# 9DoF_IMU_Module.net
KiCad netlist of a schematic drawn in EAGLE
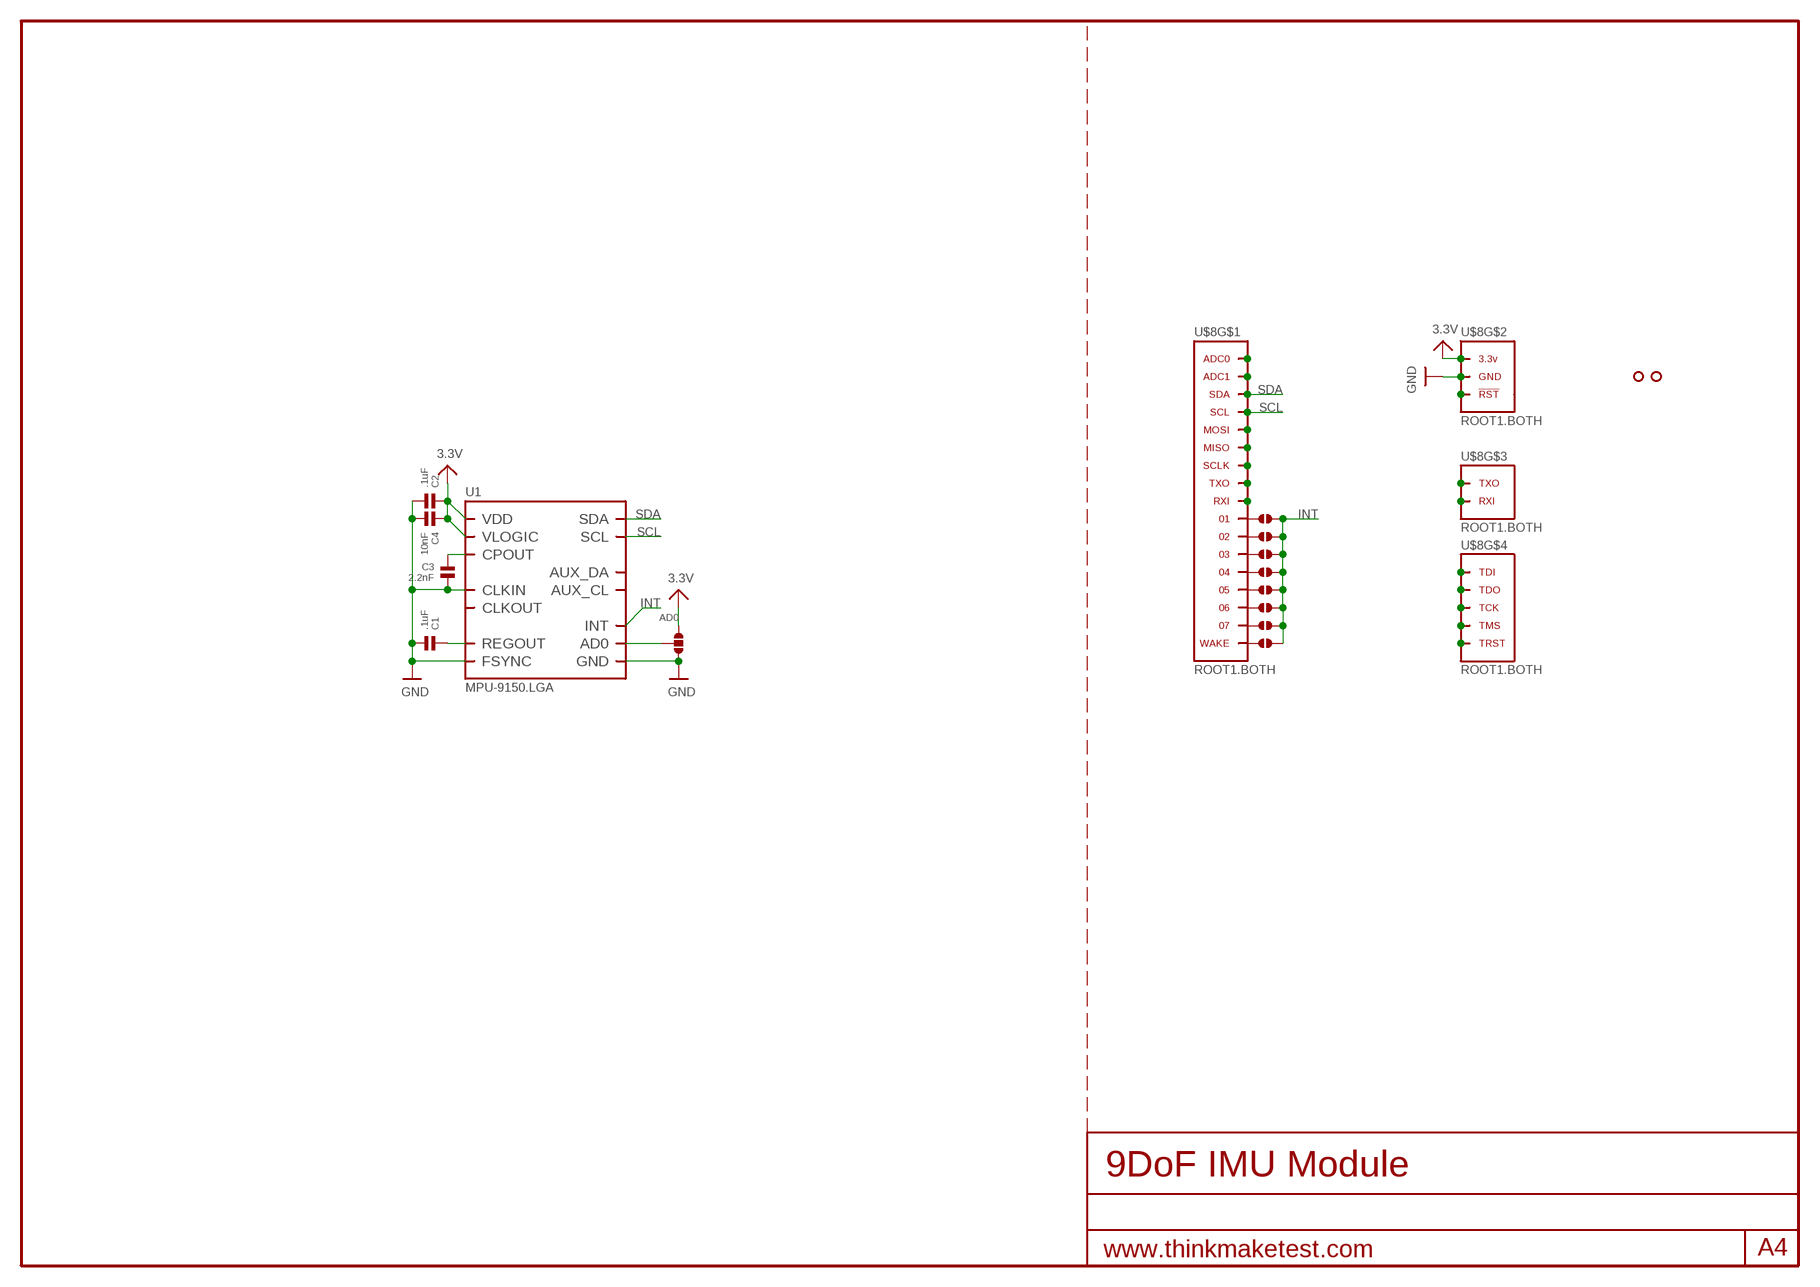
[diagram p0: schematic, sheet 1]

(export (version "E")
  (design (tool "Eeschema 10.0.6"))
  (components
    (comp (ref "AD0")
      (value "SOLDERJUMPER.3.MED.23")
      (footprint "eagle-import:3.MED.23")
      (libsource (lib "eagle-import") (part "SOLDERJUMPER.3.MED.23"))
    )
    (comp (ref "C1")
      (value ".1uF")
      (footprint "eagle-import:0603")
      (libsource (lib "eagle-import") (part "CAPACITOR.0603"))
    )
    (comp (ref "C2")
      (value ".1uF")
      (footprint "eagle-import:0603")
      (libsource (lib "eagle-import") (part "CAPACITOR.0603"))
    )
    (comp (ref "C3")
      (value "2.2nF")
      (footprint "eagle-import:0603")
      (libsource (lib "eagle-import") (part "CAPACITOR.0603"))
    )
    (comp (ref "C4")
      (value "10nF")
      (footprint "eagle-import:0603")
      (libsource (lib "eagle-import") (part "CAPACITOR.0603"))
    )
    (comp (ref "J1")
      (value "SOLDERJUMPER.2.SML")
      (footprint "eagle-import:2.SML")
      (libsource (lib "eagle-import") (part "SOLDERJUMPER.2.SML"))
    )
    (comp (ref "J2")
      (value "SOLDERJUMPER.2.SML")
      (footprint "eagle-import:2.SML")
      (libsource (lib "eagle-import") (part "SOLDERJUMPER.2.SML"))
    )
    (comp (ref "J3")
      (value "SOLDERJUMPER.2.SML")
      (footprint "eagle-import:2.SML")
      (libsource (lib "eagle-import") (part "SOLDERJUMPER.2.SML"))
    )
    (comp (ref "J4")
      (value "SOLDERJUMPER.2.SML")
      (footprint "eagle-import:2.SML")
      (libsource (lib "eagle-import") (part "SOLDERJUMPER.2.SML"))
    )
    (comp (ref "J5")
      (value "SOLDERJUMPER.2.SML")
      (footprint "eagle-import:2.SML")
      (libsource (lib "eagle-import") (part "SOLDERJUMPER.2.SML"))
    )
    (comp (ref "J6")
      (value "SOLDERJUMPER.2.SML")
      (footprint "eagle-import:2.SML")
      (libsource (lib "eagle-import") (part "SOLDERJUMPER.2.SML"))
    )
    (comp (ref "J7")
      (value "SOLDERJUMPER.2.SML")
      (footprint "eagle-import:2.SML")
      (libsource (lib "eagle-import") (part "SOLDERJUMPER.2.SML"))
    )
    (comp (ref "J8")
      (value "SOLDERJUMPER.2.SML")
      (footprint "eagle-import:2.SML")
      (libsource (lib "eagle-import") (part "SOLDERJUMPER.2.SML"))
    )
    (comp (ref "U$2")
      (value "HOLE.#2")
      (footprint "eagle-import:#2")
      (libsource (lib "eagle-import") (part "HOLE.#2"))
    )
    (comp (ref "U$8")
      (value "ROOT1.BOTH")
      (footprint "eagle-import:ROOT1.BOTH")
      (libsource (lib "eagle-import") (part "ROOT1.BOTH"))
    )
    (comp (ref "U$12")
      (value "HOLE.#2")
      (footprint "eagle-import:#2")
      (libsource (lib "eagle-import") (part "HOLE.#2"))
    )
    (comp (ref "U1")
      (value "MPU-9150.LGA")
      (footprint "eagle-import:LGA.24.4X4")
      (libsource (lib "eagle-import") (part "MPU-9150.LGA"))
    )
  )
  (nets
    (net (code "1") (name "/INT") (class "Default")
      (node (ref "J1") (pin "2") (pinfunction "2_2") (pintype "bidirectional"))
      (node (ref "J2") (pin "2") (pinfunction "2_2") (pintype "bidirectional"))
      (node (ref "J3") (pin "2") (pinfunction "2_2") (pintype "bidirectional"))
      (node (ref "J4") (pin "2") (pinfunction "2_2") (pintype "bidirectional"))
      (node (ref "J5") (pin "2") (pinfunction "2_2") (pintype "bidirectional"))
      (node (ref "J6") (pin "2") (pinfunction "2_2") (pintype "bidirectional"))
      (node (ref "J7") (pin "2") (pinfunction "2_2") (pintype "bidirectional"))
      (node (ref "J8") (pin "2") (pinfunction "2_2") (pintype "bidirectional"))
      (node (ref "U1") (pin "12") (pinfunction "INT_12") (pintype "bidirectional"))
    )
    (net (code "2") (name "/SCL") (class "Default")
      (node (ref "U$8") (pin "SCL") (pinfunction "SCL_SCL") (pintype "bidirectional"))
      (node (ref "U$8") (pin "SCL@1") (pinfunction "SCL_SCL@1") (pintype "bidirectional"))
      (node (ref "U$8") (pin "SCL@VIA") (pinfunction "SCL_SCL@VIA") (pintype "bidirectional"))
      (node (ref "U1") (pin "23") (pinfunction "SCL_23") (pintype "bidirectional"))
    )
    (net (code "3") (name "/SDA") (class "Default")
      (node (ref "U$8") (pin "SDA") (pinfunction "SDA_SDA") (pintype "bidirectional"))
      (node (ref "U$8") (pin "SDA@1") (pinfunction "SDA_SDA@1") (pintype "bidirectional"))
      (node (ref "U$8") (pin "SDA@VIA") (pinfunction "SDA_SDA@VIA") (pintype "bidirectional"))
      (node (ref "U1") (pin "24") (pinfunction "SDA_24") (pintype "bidirectional"))
    )
    (net (code "4") (name "3.3V") (class "Default")
      (node (ref "AD0") (pin "1") (pinfunction "1_1") (pintype "bidirectional"))
      (node (ref "C2") (pin "1") (pinfunction "1_1") (pintype "bidirectional"))
      (node (ref "C4") (pin "1") (pinfunction "1_1") (pintype "bidirectional"))
      (node (ref "U$8") (pin "3.3V@1") (pinfunction "3.3V_3.3V@1") (pintype "bidirectional"))
      (node (ref "U$8") (pin "3.3V@10") (pinfunction "3.3V_3.3V@10") (pintype "bidirectional"))
      (node (ref "U$8") (pin "3.3V@11") (pinfunction "3.3V_3.3V@11") (pintype "bidirectional"))
      (node (ref "U$8") (pin "3.3V@12") (pinfunction "3.3V_3.3V@12") (pintype "bidirectional"))
      (node (ref "U$8") (pin "3.3V@13") (pinfunction "3.3V_3.3V@13") (pintype "bidirectional"))
      (node (ref "U$8") (pin "3.3V@14") (pinfunction "3.3V_3.3V@14") (pintype "bidirectional"))
      (node (ref "U$8") (pin "3.3V@15") (pinfunction "3.3V_3.3V@15") (pintype "bidirectional"))
      (node (ref "U$8") (pin "3.3V@16") (pinfunction "3.3V_3.3V@16") (pintype "bidirectional"))
      (node (ref "U$8") (pin "3.3V@17") (pinfunction "3.3V_3.3V@17") (pintype "bidirectional"))
      (node (ref "U$8") (pin "3.3V@18") (pinfunction "3.3V_3.3V@18") (pintype "bidirectional"))
      (node (ref "U$8") (pin "3.3V@19") (pinfunction "3.3V_3.3V@19") (pintype "bidirectional"))
      (node (ref "U$8") (pin "3.3V@2") (pinfunction "3.3V_3.3V@2") (pintype "bidirectional"))
      (node (ref "U$8") (pin "3.3V@20") (pinfunction "3.3V_3.3V@20") (pintype "bidirectional"))
      (node (ref "U$8") (pin "3.3V@21") (pinfunction "3.3V_3.3V@21") (pintype "bidirectional"))
      (node (ref "U$8") (pin "3.3V@22") (pinfunction "3.3V_3.3V@22") (pintype "bidirectional"))
      (node (ref "U$8") (pin "3.3V@23") (pinfunction "3.3V_3.3V@23") (pintype "bidirectional"))
      (node (ref "U$8") (pin "3.3V@24") (pinfunction "3.3V_3.3V@24") (pintype "bidirectional"))
      (node (ref "U$8") (pin "3.3V@3") (pinfunction "3.3V_3.3V@3") (pintype "bidirectional"))
      (node (ref "U$8") (pin "3.3V@4") (pinfunction "3.3V_3.3V@4") (pintype "bidirectional"))
      (node (ref "U$8") (pin "3.3V@5") (pinfunction "3.3V_3.3V@5") (pintype "bidirectional"))
      (node (ref "U$8") (pin "3.3V@6") (pinfunction "3.3V_3.3V@6") (pintype "bidirectional"))
      (node (ref "U$8") (pin "3.3V@7") (pinfunction "3.3V_3.3V@7") (pintype "bidirectional"))
      (node (ref "U$8") (pin "3.3V@8") (pinfunction "3.3V_3.3V@8") (pintype "bidirectional"))
      (node (ref "U$8") (pin "3.3V@9") (pinfunction "3.3V_3.3V@9") (pintype "bidirectional"))
      (node (ref "U$8") (pin "3.3V@VIA") (pinfunction "3.3V_3.3V@VIA") (pintype "bidirectional"))
      (node (ref "U1") (pin "13") (pinfunction "VDD_13") (pintype "bidirectional"))
      (node (ref "U1") (pin "3") (pinfunction "VDD_3") (pintype "bidirectional"))
      (node (ref "U1") (pin "8") (pinfunction "VLOGIC_8") (pintype "bidirectional"))
    )
    (net (code "5") (name "GND") (class "Default")
      (node (ref "AD0") (pin "3") (pinfunction "3_3") (pintype "bidirectional"))
      (node (ref "C1") (pin "2") (pinfunction "2_2") (pintype "bidirectional"))
      (node (ref "C2") (pin "2") (pinfunction "2_2") (pintype "bidirectional"))
      (node (ref "C3") (pin "2") (pinfunction "2_2") (pintype "bidirectional"))
      (node (ref "C4") (pin "2") (pinfunction "2_2") (pintype "bidirectional"))
      (node (ref "U$8") (pin "GND@1") (pinfunction "GND_GND@1") (pintype "bidirectional"))
      (node (ref "U$8") (pin "GND@10") (pinfunction "GND_GND@10") (pintype "bidirectional"))
      (node (ref "U$8") (pin "GND@11") (pinfunction "GND_GND@11") (pintype "bidirectional"))
      (node (ref "U$8") (pin "GND@12") (pinfunction "GND_GND@12") (pintype "bidirectional"))
      (node (ref "U$8") (pin "GND@13") (pinfunction "GND_GND@13") (pintype "bidirectional"))
      (node (ref "U$8") (pin "GND@14") (pinfunction "GND_GND@14") (pintype "bidirectional"))
      (node (ref "U$8") (pin "GND@15") (pinfunction "GND_GND@15") (pintype "bidirectional"))
      (node (ref "U$8") (pin "GND@16") (pinfunction "GND_GND@16") (pintype "bidirectional"))
      (node (ref "U$8") (pin "GND@17") (pinfunction "GND_GND@17") (pintype "bidirectional"))
      (node (ref "U$8") (pin "GND@18") (pinfunction "GND_GND@18") (pintype "bidirectional"))
      (node (ref "U$8") (pin "GND@19") (pinfunction "GND_GND@19") (pintype "bidirectional"))
      (node (ref "U$8") (pin "GND@2") (pinfunction "GND_GND@2") (pintype "bidirectional"))
      (node (ref "U$8") (pin "GND@20") (pinfunction "GND_GND@20") (pintype "bidirectional"))
      (node (ref "U$8") (pin "GND@21") (pinfunction "GND_GND@21") (pintype "bidirectional"))
      (node (ref "U$8") (pin "GND@22") (pinfunction "GND_GND@22") (pintype "bidirectional"))
      (node (ref "U$8") (pin "GND@23") (pinfunction "GND_GND@23") (pintype "bidirectional"))
      (node (ref "U$8") (pin "GND@24") (pinfunction "GND_GND@24") (pintype "bidirectional"))
      (node (ref "U$8") (pin "GND@25") (pinfunction "GND_GND@25") (pintype "bidirectional"))
      (node (ref "U$8") (pin "GND@26") (pinfunction "GND_GND@26") (pintype "bidirectional"))
      (node (ref "U$8") (pin "GND@3") (pinfunction "GND_GND@3") (pintype "bidirectional"))
      (node (ref "U$8") (pin "GND@4") (pinfunction "GND_GND@4") (pintype "bidirectional"))
      (node (ref "U$8") (pin "GND@5") (pinfunction "GND_GND@5") (pintype "bidirectional"))
      (node (ref "U$8") (pin "GND@6") (pinfunction "GND_GND@6") (pintype "bidirectional"))
      (node (ref "U$8") (pin "GND@7") (pinfunction "GND_GND@7") (pintype "bidirectional"))
      (node (ref "U$8") (pin "GND@8") (pinfunction "GND_GND@8") (pintype "bidirectional"))
      (node (ref "U$8") (pin "GND@9") (pinfunction "GND_GND@9") (pintype "bidirectional"))
      (node (ref "U$8") (pin "GND@VIA") (pinfunction "GND_GND@VIA") (pintype "bidirectional"))
      (node (ref "U1") (pin "1") (pinfunction "CLKIN_1") (pintype "bidirectional"))
      (node (ref "U1") (pin "11") (pinfunction "FSYNC_11") (pintype "bidirectional"))
      (node (ref "U1") (pin "15") (pinfunction "GND_15") (pintype "bidirectional"))
      (node (ref "U1") (pin "17") (pinfunction "GND_17") (pintype "bidirectional"))
      (node (ref "U1") (pin "18") (pinfunction "GND_18") (pintype "bidirectional"))
    )
    (net (code "6") (name "Net-(J1-Pad1)") (class "Default")
      (node (ref "J1") (pin "1") (pinfunction "1_1") (pintype "bidirectional"))
      (node (ref "U$8") (pin "01") (pinfunction "01_01") (pintype "bidirectional"))
      (node (ref "U$8") (pin "01@1") (pinfunction "01_01@1") (pintype "bidirectional"))
      (node (ref "U$8") (pin "01@VIA") (pinfunction "01_01@VIA") (pintype "bidirectional"))
    )
    (net (code "7") (name "Net-(J2-Pad1)") (class "Default")
      (node (ref "J2") (pin "1") (pinfunction "1_1") (pintype "bidirectional"))
      (node (ref "U$8") (pin "02") (pinfunction "02_02") (pintype "bidirectional"))
      (node (ref "U$8") (pin "02@1") (pinfunction "02_02@1") (pintype "bidirectional"))
      (node (ref "U$8") (pin "02@VIA") (pinfunction "02_02@VIA") (pintype "bidirectional"))
    )
    (net (code "8") (name "Net-(J3-Pad1)") (class "Default")
      (node (ref "J3") (pin "1") (pinfunction "1_1") (pintype "bidirectional"))
      (node (ref "U$8") (pin "03") (pinfunction "03_03") (pintype "bidirectional"))
      (node (ref "U$8") (pin "03@1") (pinfunction "03_03@1") (pintype "bidirectional"))
      (node (ref "U$8") (pin "03@VIA") (pinfunction "03_03@VIA") (pintype "bidirectional"))
    )
    (net (code "9") (name "Net-(J4-Pad1)") (class "Default")
      (node (ref "J4") (pin "1") (pinfunction "1_1") (pintype "bidirectional"))
      (node (ref "U$8") (pin "04") (pinfunction "04_04") (pintype "bidirectional"))
      (node (ref "U$8") (pin "04@1") (pinfunction "04_04@1") (pintype "bidirectional"))
      (node (ref "U$8") (pin "04@VIA") (pinfunction "04_04@VIA") (pintype "bidirectional"))
    )
    (net (code "10") (name "Net-(J5-Pad1)") (class "Default")
      (node (ref "J5") (pin "1") (pinfunction "1_1") (pintype "bidirectional"))
      (node (ref "U$8") (pin "05") (pinfunction "05_05") (pintype "bidirectional"))
      (node (ref "U$8") (pin "05@1") (pinfunction "05_05@1") (pintype "bidirectional"))
      (node (ref "U$8") (pin "05@VIA") (pinfunction "05_05@VIA") (pintype "bidirectional"))
    )
    (net (code "11") (name "Net-(J6-Pad1)") (class "Default")
      (node (ref "J6") (pin "1") (pinfunction "1_1") (pintype "bidirectional"))
      (node (ref "U$8") (pin "06") (pinfunction "06_06") (pintype "bidirectional"))
      (node (ref "U$8") (pin "06@1") (pinfunction "06_06@1") (pintype "bidirectional"))
      (node (ref "U$8") (pin "06@VIA") (pinfunction "06_06@VIA") (pintype "bidirectional"))
    )
    (net (code "12") (name "Net-(J7-Pad1)") (class "Default")
      (node (ref "J7") (pin "1") (pinfunction "1_1") (pintype "bidirectional"))
      (node (ref "U$8") (pin "07") (pinfunction "07_07") (pintype "bidirectional"))
      (node (ref "U$8") (pin "07@1") (pinfunction "07_07@1") (pintype "bidirectional"))
      (node (ref "U$8") (pin "07@VIA") (pinfunction "07_07@VIA") (pintype "bidirectional"))
    )
    (net (code "13") (name "Net-(J8-Pad1)") (class "Default")
      (node (ref "J8") (pin "1") (pinfunction "1_1") (pintype "bidirectional"))
      (node (ref "U$8") (pin "WAKE") (pinfunction "WAKE_WAKE") (pintype "bidirectional"))
      (node (ref "U$8") (pin "WAKE@1") (pinfunction "WAKE_WAKE@1") (pintype "bidirectional"))
      (node (ref "U$8") (pin "WAKE@VIA") (pinfunction "WAKE_WAKE@VIA") (pintype "bidirectional"))
    )
    (net (code "14") (name "Net-(U$8-PadADC0)") (class "Default")
      (node (ref "U$8") (pin "ADC0") (pinfunction "ADC0_ADC0") (pintype "bidirectional"))
      (node (ref "U$8") (pin "ADC0@1") (pinfunction "ADC0_ADC0@1") (pintype "bidirectional"))
      (node (ref "U$8") (pin "ADC0@VIA") (pinfunction "ADC0_ADC0@VIA") (pintype "bidirectional"))
    )
    (net (code "15") (name "Net-(U$8-PadADC1)") (class "Default")
      (node (ref "U$8") (pin "ADC1") (pinfunction "ADC1_ADC1") (pintype "bidirectional"))
      (node (ref "U$8") (pin "ADC1@1") (pinfunction "ADC1_ADC1@1") (pintype "bidirectional"))
      (node (ref "U$8") (pin "ADC1@VIA") (pinfunction "ADC1_ADC1@VIA") (pintype "bidirectional"))
    )
    (net (code "16") (name "Net-(U$8-PadMISO)") (class "Default")
      (node (ref "U$8") (pin "MISO") (pinfunction "MISO_MISO") (pintype "bidirectional"))
      (node (ref "U$8") (pin "MISO@1") (pinfunction "MISO_MISO@1") (pintype "bidirectional"))
      (node (ref "U$8") (pin "MISO@VIA") (pinfunction "MISO_MISO@VIA") (pintype "bidirectional"))
    )
    (net (code "17") (name "Net-(U$8-PadMOSI)") (class "Default")
      (node (ref "U$8") (pin "MOSI") (pinfunction "MOSI_MOSI") (pintype "bidirectional"))
      (node (ref "U$8") (pin "MOSI@1") (pinfunction "MOSI_MOSI@1") (pintype "bidirectional"))
      (node (ref "U$8") (pin "MOSI@VIA") (pinfunction "MOSI_MOSI@VIA") (pintype "bidirectional"))
    )
    (net (code "18") (name "Net-(U$8-PadRXI)") (class "Default")
      (node (ref "U$8") (pin "RXI") (pinfunction "RXI_RXI") (pintype "bidirectional"))
      (node (ref "U$8") (pin "RXI@1") (pinfunction "RXI_RXI@1") (pintype "bidirectional"))
      (node (ref "U$8") (pin "RXI@VIA") (pinfunction "RXI_RXI@VIA") (pintype "bidirectional"))
    )
    (net (code "19") (name "Net-(U$8-PadSCLK)") (class "Default")
      (node (ref "U$8") (pin "SCLK") (pinfunction "SCLK_SCLK") (pintype "bidirectional"))
      (node (ref "U$8") (pin "SCLK@1") (pinfunction "SCLK_SCLK@1") (pintype "bidirectional"))
      (node (ref "U$8") (pin "SCLK@VIA") (pinfunction "SCLK_SCLK@VIA") (pintype "bidirectional"))
    )
    (net (code "20") (name "Net-(U$8-PadTCK)") (class "Default")
      (node (ref "U$8") (pin "TCK") (pinfunction "TCK_TCK") (pintype "bidirectional"))
      (node (ref "U$8") (pin "TCK@1") (pinfunction "TCK_TCK@1") (pintype "bidirectional"))
      (node (ref "U$8") (pin "TCK@VIA") (pinfunction "TCK_TCK@VIA") (pintype "bidirectional"))
    )
    (net (code "21") (name "Net-(U$8-PadTDI)") (class "Default")
      (node (ref "U$8") (pin "TDI") (pinfunction "TDI_TDI") (pintype "bidirectional"))
      (node (ref "U$8") (pin "TDI@1") (pinfunction "TDI_TDI@1") (pintype "bidirectional"))
      (node (ref "U$8") (pin "TDI@VIA") (pinfunction "TDI_TDI@VIA") (pintype "bidirectional"))
    )
    (net (code "22") (name "Net-(U$8-PadTDO)") (class "Default")
      (node (ref "U$8") (pin "TDO") (pinfunction "TDO_TDO") (pintype "bidirectional"))
      (node (ref "U$8") (pin "TDO@1") (pinfunction "TDO_TDO@1") (pintype "bidirectional"))
      (node (ref "U$8") (pin "TDO@VIA") (pinfunction "TDO_TDO@VIA") (pintype "bidirectional"))
    )
    (net (code "23") (name "Net-(U$8-PadTMS)") (class "Default")
      (node (ref "U$8") (pin "TMS") (pinfunction "TMS_TMS") (pintype "bidirectional"))
      (node (ref "U$8") (pin "TMS@1") (pinfunction "TMS_TMS@1") (pintype "bidirectional"))
      (node (ref "U$8") (pin "TMS@VIA") (pinfunction "TMS_TMS@VIA") (pintype "bidirectional"))
    )
    (net (code "24") (name "Net-(U$8-PadTRST)") (class "Default")
      (node (ref "U$8") (pin "TRST") (pinfunction "TRST_TRST") (pintype "bidirectional"))
      (node (ref "U$8") (pin "TRST@1") (pinfunction "TRST_TRST@1") (pintype "bidirectional"))
      (node (ref "U$8") (pin "TRST@VIA") (pinfunction "TRST_TRST@VIA") (pintype "bidirectional"))
    )
    (net (code "25") (name "Net-(U$8-PadTXO)") (class "Default")
      (node (ref "U$8") (pin "TXO") (pinfunction "TXO_TXO") (pintype "bidirectional"))
      (node (ref "U$8") (pin "TXO@1") (pinfunction "TXO_TXO@1") (pintype "bidirectional"))
      (node (ref "U$8") (pin "TXO@VIA") (pinfunction "TXO_TXO@VIA") (pintype "bidirectional"))
    )
    (net (code "26") (name "Net-(U$8B-~{RST}-PadRST)") (class "Default")
      (node (ref "U$8") (pin "RST") (pinfunction "~{RST}_RST") (pintype "bidirectional"))
      (node (ref "U$8") (pin "RST@1") (pinfunction "~{RST}_RST@1") (pintype "bidirectional"))
      (node (ref "U$8") (pin "RST@VIA") (pinfunction "~{RST}_RST@VIA") (pintype "bidirectional"))
    )
    (net (code "27") (name "Net-(U$8C-RXI-PadRXI.DBG)") (class "Default")
      (node (ref "U$8") (pin "RXI.DBG") (pinfunction "RXI_RXI.DBG") (pintype "bidirectional"))
      (node (ref "U$8") (pin "RXI.DBG@1") (pinfunction "RXI_RXI.DBG@1") (pintype "bidirectional"))
      (node (ref "U$8") (pin "RXI.DBG@VIA") (pinfunction "RXI_RXI.DBG@VIA") (pintype "bidirectional"))
    )
    (net (code "28") (name "Net-(U$8C-TXO-PadTXO.DBG)") (class "Default")
      (node (ref "U$8") (pin "TXO.DBG") (pinfunction "TXO_TXO.DBG") (pintype "bidirectional"))
      (node (ref "U$8") (pin "TXO.DBG@1") (pinfunction "TXO_TXO.DBG@1") (pintype "bidirectional"))
      (node (ref "U$8") (pin "TXO.DBG@VIA") (pinfunction "TXO_TXO.DBG@VIA") (pintype "bidirectional"))
    )
    (net (code "29") (name "Net-(U1-AD0)") (class "Default")
      (node (ref "AD0") (pin "2") (pinfunction "2_2") (pintype "bidirectional"))
      (node (ref "U1") (pin "9") (pinfunction "AD0_9") (pintype "bidirectional"))
    )
    (net (code "30") (name "Net-(U1-CPOUT)") (class "Default")
      (node (ref "C3") (pin "1") (pinfunction "1_1") (pintype "bidirectional"))
      (node (ref "U1") (pin "20") (pinfunction "CPOUT_20") (pintype "bidirectional"))
    )
    (net (code "31") (name "Net-(U1-REGOUT)") (class "Default")
      (node (ref "C1") (pin "1") (pinfunction "1_1") (pintype "bidirectional"))
      (node (ref "U1") (pin "10") (pinfunction "REGOUT_10") (pintype "bidirectional"))
    )
    (net (code "32") (name "unconnected-(U1-AUX_CL-Pad7)") (class "Default")
      (node (ref "U1") (pin "7") (pinfunction "AUX_CL_7") (pintype "bidirectional"))
    )
    (net (code "33") (name "unconnected-(U1-AUX_DA-Pad6)") (class "Default")
      (node (ref "U1") (pin "6") (pinfunction "AUX_DA_6") (pintype "bidirectional"))
    )
    (net (code "34") (name "unconnected-(U1-CLKOUT-Pad22)") (class "Default")
      (node (ref "U1") (pin "22") (pinfunction "CLKOUT_22") (pintype "bidirectional"))
    )
  )
)
